# M622X.net
KiCad netlist of a schematic drawn in EAGLE
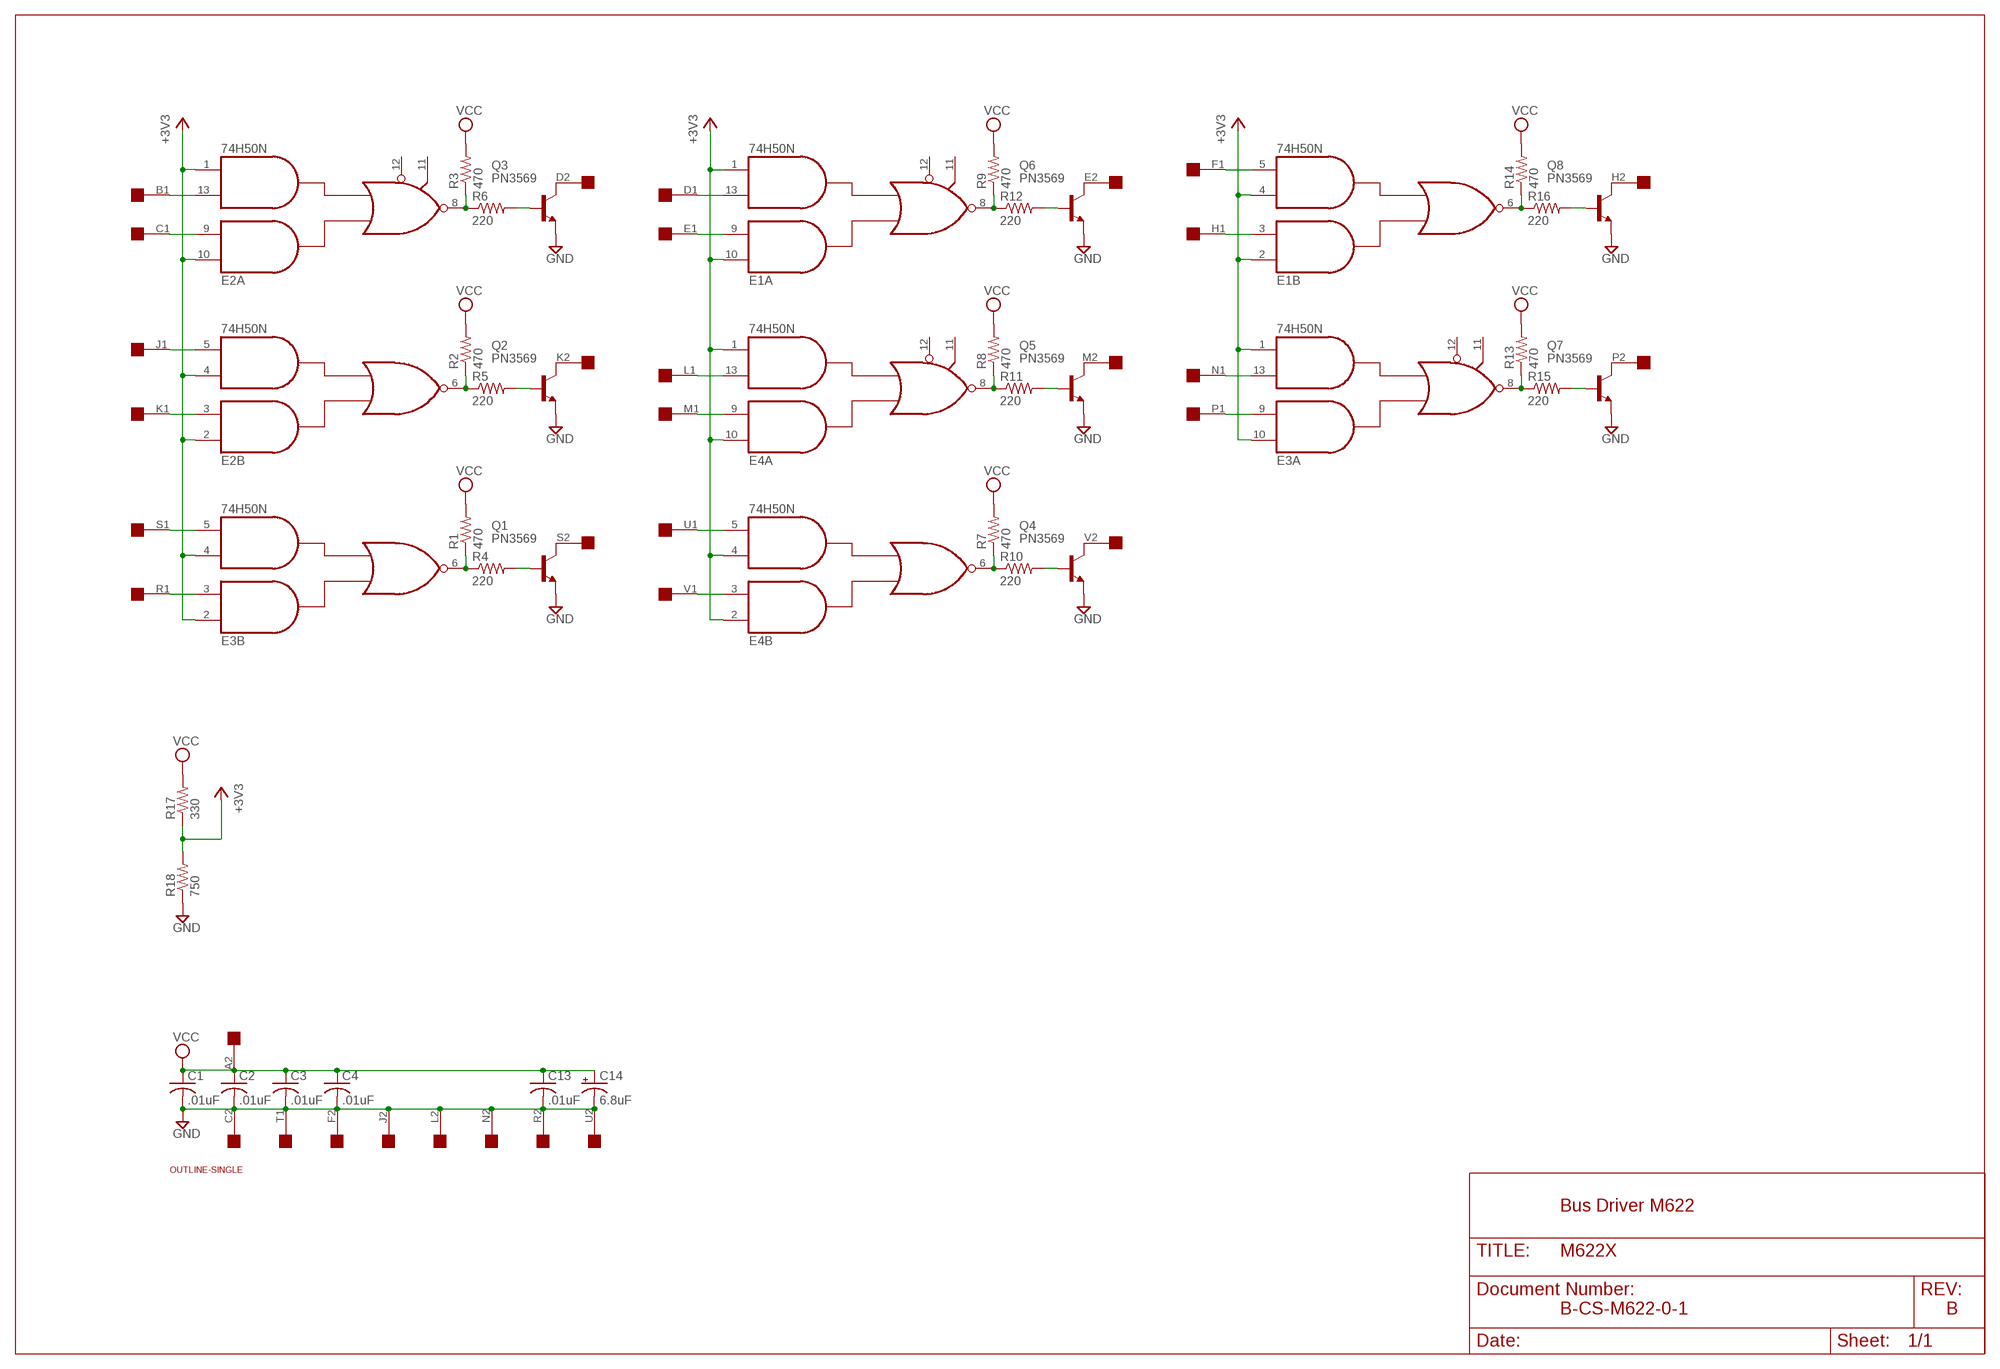
[diagram p0: schematic, sheet 1]

(export (version "E")
  (design (tool "Eeschema 10.0.6"))
  (components
    (comp (ref "C1")
      (value ".01uF")
      (footprint "eagle-import:C050-025X075")
      (libsource (lib "eagle-import") (part "C-US050-025X075"))
    )
    (comp (ref "C2")
      (value ".01uF")
      (footprint "eagle-import:C050-025X075")
      (libsource (lib "eagle-import") (part "C-US050-025X075"))
    )
    (comp (ref "C3")
      (value ".01uF")
      (footprint "eagle-import:C050-025X075")
      (libsource (lib "eagle-import") (part "C-US050-025X075"))
    )
    (comp (ref "C4")
      (value ".01uF")
      (footprint "eagle-import:C050-025X075")
      (libsource (lib "eagle-import") (part "C-US050-025X075"))
    )
    (comp (ref "C13")
      (value ".01uF")
      (footprint "eagle-import:C050-025X075")
      (libsource (lib "eagle-import") (part "C-US050-025X075"))
    )
    (comp (ref "C14")
      (value "6.8uF")
      (footprint "eagle-import:E12-8")
      (libsource (lib "eagle-import") (part "CPOL-USE20-8AXIAL"))
    )
    (comp (ref "E1")
      (value "74H50N")
      (footprint "eagle-import:DIL14")
      (libsource (lib "eagle-import") (part "7450N"))
    )
    (comp (ref "E2")
      (value "74H50N")
      (footprint "eagle-import:DIL14")
      (libsource (lib "eagle-import") (part "7450N"))
    )
    (comp (ref "E3")
      (value "74H50N")
      (footprint "eagle-import:DIL14")
      (libsource (lib "eagle-import") (part "7450N"))
    )
    (comp (ref "E4")
      (value "74H50N")
      (footprint "eagle-import:DIL14")
      (libsource (lib "eagle-import") (part "7450N"))
    )
    (comp (ref "Q1")
      (value "PN3569")
      (footprint "eagle-import:TO5")
      (libsource (lib "eagle-import") (part "2N2102"))
    )
    (comp (ref "Q2")
      (value "PN3569")
      (footprint "eagle-import:TO5")
      (libsource (lib "eagle-import") (part "2N2102"))
    )
    (comp (ref "Q3")
      (value "PN3569")
      (footprint "eagle-import:TO5")
      (libsource (lib "eagle-import") (part "2N2102"))
    )
    (comp (ref "Q4")
      (value "PN3569")
      (footprint "eagle-import:TO5")
      (libsource (lib "eagle-import") (part "2N2102"))
    )
    (comp (ref "Q5")
      (value "PN3569")
      (footprint "eagle-import:TO5")
      (libsource (lib "eagle-import") (part "2N2102"))
    )
    (comp (ref "Q6")
      (value "PN3569")
      (footprint "eagle-import:TO5")
      (libsource (lib "eagle-import") (part "2N2102"))
    )
    (comp (ref "Q7")
      (value "PN3569")
      (footprint "eagle-import:TO5")
      (libsource (lib "eagle-import") (part "2N2102"))
    )
    (comp (ref "Q8")
      (value "PN3569")
      (footprint "eagle-import:TO5")
      (libsource (lib "eagle-import") (part "2N2102"))
    )
    (comp (ref "R1")
      (value "470")
      (footprint "eagle-import:0207_10")
      (libsource (lib "eagle-import") (part "R-US_0207/10"))
    )
    (comp (ref "R2")
      (value "470")
      (footprint "eagle-import:0207_10")
      (libsource (lib "eagle-import") (part "R-US_0207/10"))
    )
    (comp (ref "R3")
      (value "470")
      (footprint "eagle-import:0207_10")
      (libsource (lib "eagle-import") (part "R-US_0207/10"))
    )
    (comp (ref "R4")
      (value "220")
      (footprint "eagle-import:0207_10")
      (libsource (lib "eagle-import") (part "R-US_0207/10"))
    )
    (comp (ref "R5")
      (value "220")
      (footprint "eagle-import:0207_10")
      (libsource (lib "eagle-import") (part "R-US_0207/10"))
    )
    (comp (ref "R6")
      (value "220")
      (footprint "eagle-import:0207_10")
      (libsource (lib "eagle-import") (part "R-US_0207/10"))
    )
    (comp (ref "R7")
      (value "470")
      (footprint "eagle-import:0207_10")
      (libsource (lib "eagle-import") (part "R-US_0207/10"))
    )
    (comp (ref "R8")
      (value "470")
      (footprint "eagle-import:0207_10")
      (libsource (lib "eagle-import") (part "R-US_0207/10"))
    )
    (comp (ref "R9")
      (value "470")
      (footprint "eagle-import:0207_10")
      (libsource (lib "eagle-import") (part "R-US_0207/10"))
    )
    (comp (ref "R10")
      (value "220")
      (footprint "eagle-import:0207_10")
      (libsource (lib "eagle-import") (part "R-US_0207/10"))
    )
    (comp (ref "R11")
      (value "220")
      (footprint "eagle-import:0207_10")
      (libsource (lib "eagle-import") (part "R-US_0207/10"))
    )
    (comp (ref "R12")
      (value "220")
      (footprint "eagle-import:0207_10")
      (libsource (lib "eagle-import") (part "R-US_0207/10"))
    )
    (comp (ref "R13")
      (value "470")
      (footprint "eagle-import:0207_10")
      (libsource (lib "eagle-import") (part "R-US_0207/10"))
    )
    (comp (ref "R14")
      (value "470")
      (footprint "eagle-import:0207_10")
      (libsource (lib "eagle-import") (part "R-US_0207/10"))
    )
    (comp (ref "R15")
      (value "220")
      (footprint "eagle-import:0207_10")
      (libsource (lib "eagle-import") (part "R-US_0207/10"))
    )
    (comp (ref "R16")
      (value "220")
      (footprint "eagle-import:0207_10")
      (libsource (lib "eagle-import") (part "R-US_0207/10"))
    )
    (comp (ref "R17")
      (value "330")
      (footprint "eagle-import:0207_10")
      (libsource (lib "eagle-import") (part "R-US_0207/10"))
    )
    (comp (ref "R18")
      (value "750")
      (footprint "eagle-import:0207_10")
      (libsource (lib "eagle-import") (part "R-US_0207/10"))
    )
    (comp (ref "U$1")
      (value "SINGLE")
      (footprint "eagle-import:EDGE-CON2")
      (libsource (lib "eagle-import") (part "SINGLE"))
    )
    (comp (ref "U$4")
      (value "OUTLINE-SINGLE")
      (footprint "eagle-import:SINGLE")
      (libsource (lib "eagle-import") (part "OUTLINE-SINGLE"))
    )
  )
  (nets
    (net (code "1") (name "+3V3") (class "Default")
      (node (ref "E1") (pin "1") (pinfunction "I4_1") (pintype "input"))
      (node (ref "E1") (pin "10") (pinfunction "I1_10") (pintype "input"))
      (node (ref "E1") (pin "2") (pinfunction "I1_2") (pintype "input"))
      (node (ref "E1") (pin "4") (pinfunction "I3_4") (pintype "input"))
      (node (ref "E2") (pin "1") (pinfunction "I4_1") (pintype "input"))
      (node (ref "E2") (pin "10") (pinfunction "I1_10") (pintype "input"))
      (node (ref "E2") (pin "2") (pinfunction "I1_2") (pintype "input"))
      (node (ref "E2") (pin "4") (pinfunction "I3_4") (pintype "input"))
      (node (ref "E3") (pin "1") (pinfunction "I4_1") (pintype "input"))
      (node (ref "E3") (pin "10") (pinfunction "I1_10") (pintype "input"))
      (node (ref "E3") (pin "2") (pinfunction "I1_2") (pintype "input"))
      (node (ref "E3") (pin "4") (pinfunction "I3_4") (pintype "input"))
      (node (ref "E4") (pin "1") (pinfunction "I4_1") (pintype "input"))
      (node (ref "E4") (pin "10") (pinfunction "I1_10") (pintype "input"))
      (node (ref "E4") (pin "2") (pinfunction "I1_2") (pintype "input"))
      (node (ref "E4") (pin "4") (pinfunction "I3_4") (pintype "input"))
      (node (ref "R17") (pin "1") (pinfunction "1_1") (pintype "passive"))
      (node (ref "R18") (pin "2") (pinfunction "2_2") (pintype "passive"))
    )
    (net (code "2") (name "GND") (class "Default")
      (node (ref "C1") (pin "2") (pinfunction "2_2") (pintype "passive"))
      (node (ref "C13") (pin "2") (pinfunction "2_2") (pintype "passive"))
      (node (ref "C14") (pin "-") (pinfunction "-_-") (pintype "passive"))
      (node (ref "C2") (pin "2") (pinfunction "2_2") (pintype "passive"))
      (node (ref "C3") (pin "2") (pinfunction "2_2") (pintype "passive"))
      (node (ref "C4") (pin "2") (pinfunction "2_2") (pintype "passive"))
      (node (ref "Q1") (pin "1") (pinfunction "E_1") (pintype "passive"))
      (node (ref "Q2") (pin "1") (pinfunction "E_1") (pintype "passive"))
      (node (ref "Q3") (pin "1") (pinfunction "E_1") (pintype "passive"))
      (node (ref "Q4") (pin "1") (pinfunction "E_1") (pintype "passive"))
      (node (ref "Q5") (pin "1") (pinfunction "E_1") (pintype "passive"))
      (node (ref "Q6") (pin "1") (pinfunction "E_1") (pintype "passive"))
      (node (ref "Q7") (pin "1") (pinfunction "E_1") (pintype "passive"))
      (node (ref "Q8") (pin "1") (pinfunction "E_1") (pintype "passive"))
      (node (ref "R18") (pin "1") (pinfunction "1_1") (pintype "passive"))
      (node (ref "U$1") (pin "C2") (pinfunction "1_C2") (pintype "bidirectional"))
      (node (ref "U$1") (pin "F2") (pinfunction "1_F2") (pintype "bidirectional"))
      (node (ref "U$1") (pin "J2") (pinfunction "1_J2") (pintype "bidirectional"))
      (node (ref "U$1") (pin "L2") (pinfunction "1_L2") (pintype "bidirectional"))
      (node (ref "U$1") (pin "N2") (pinfunction "1_N2") (pintype "bidirectional"))
      (node (ref "U$1") (pin "R2") (pinfunction "1_R2") (pintype "bidirectional"))
      (node (ref "U$1") (pin "T1") (pinfunction "1_T1") (pintype "bidirectional"))
      (node (ref "U$1") (pin "U2") (pinfunction "1_U2") (pintype "bidirectional"))
    )
    (net (code "3") (name "Net-(E1A-I2)") (class "Default")
      (node (ref "E1") (pin "9") (pinfunction "I2_9") (pintype "input"))
      (node (ref "U$1") (pin "E1") (pinfunction "1_E1") (pintype "bidirectional"))
    )
    (net (code "4") (name "Net-(E1A-I3)") (class "Default")
      (node (ref "E1") (pin "13") (pinfunction "I3_13") (pintype "input"))
      (node (ref "U$1") (pin "D1") (pinfunction "1_D1") (pintype "bidirectional"))
    )
    (net (code "5") (name "Net-(E1A-O)") (class "Default")
      (node (ref "E1") (pin "8") (pinfunction "O_8") (pintype "output"))
      (node (ref "R12") (pin "1") (pinfunction "1_1") (pintype "passive"))
      (node (ref "R9") (pin "1") (pinfunction "1_1") (pintype "passive"))
    )
    (net (code "6") (name "Net-(E1B-I2)") (class "Default")
      (node (ref "E1") (pin "3") (pinfunction "I2_3") (pintype "input"))
      (node (ref "U$1") (pin "H1") (pinfunction "1_H1") (pintype "bidirectional"))
    )
    (net (code "7") (name "Net-(E1B-I4)") (class "Default")
      (node (ref "E1") (pin "5") (pinfunction "I4_5") (pintype "input"))
      (node (ref "U$1") (pin "F1") (pinfunction "1_F1") (pintype "bidirectional"))
    )
    (net (code "8") (name "Net-(E1B-O)") (class "Default")
      (node (ref "E1") (pin "6") (pinfunction "O_6") (pintype "output"))
      (node (ref "R14") (pin "1") (pinfunction "1_1") (pintype "passive"))
      (node (ref "R16") (pin "1") (pinfunction "1_1") (pintype "passive"))
    )
    (net (code "9") (name "Net-(E2A-I2)") (class "Default")
      (node (ref "E2") (pin "9") (pinfunction "I2_9") (pintype "input"))
      (node (ref "U$1") (pin "C1") (pinfunction "1_C1") (pintype "bidirectional"))
    )
    (net (code "10") (name "Net-(E2A-I3)") (class "Default")
      (node (ref "E2") (pin "13") (pinfunction "I3_13") (pintype "input"))
      (node (ref "U$1") (pin "B1") (pinfunction "1_B1") (pintype "bidirectional"))
    )
    (net (code "11") (name "Net-(E2A-O)") (class "Default")
      (node (ref "E2") (pin "8") (pinfunction "O_8") (pintype "output"))
      (node (ref "R3") (pin "1") (pinfunction "1_1") (pintype "passive"))
      (node (ref "R6") (pin "1") (pinfunction "1_1") (pintype "passive"))
    )
    (net (code "12") (name "Net-(E2B-I2)") (class "Default")
      (node (ref "E2") (pin "3") (pinfunction "I2_3") (pintype "input"))
      (node (ref "U$1") (pin "K1") (pinfunction "1_K1") (pintype "bidirectional"))
    )
    (net (code "13") (name "Net-(E2B-I4)") (class "Default")
      (node (ref "E2") (pin "5") (pinfunction "I4_5") (pintype "input"))
      (node (ref "U$1") (pin "J1") (pinfunction "1_J1") (pintype "bidirectional"))
    )
    (net (code "14") (name "Net-(E2B-O)") (class "Default")
      (node (ref "E2") (pin "6") (pinfunction "O_6") (pintype "output"))
      (node (ref "R2") (pin "1") (pinfunction "1_1") (pintype "passive"))
      (node (ref "R5") (pin "1") (pinfunction "1_1") (pintype "passive"))
    )
    (net (code "15") (name "Net-(E3A-I2)") (class "Default")
      (node (ref "E3") (pin "9") (pinfunction "I2_9") (pintype "input"))
      (node (ref "U$1") (pin "P1") (pinfunction "1_P1") (pintype "bidirectional"))
    )
    (net (code "16") (name "Net-(E3A-I3)") (class "Default")
      (node (ref "E3") (pin "13") (pinfunction "I3_13") (pintype "input"))
      (node (ref "U$1") (pin "N1") (pinfunction "1_N1") (pintype "bidirectional"))
    )
    (net (code "17") (name "Net-(E3A-O)") (class "Default")
      (node (ref "E3") (pin "8") (pinfunction "O_8") (pintype "output"))
      (node (ref "R13") (pin "1") (pinfunction "1_1") (pintype "passive"))
      (node (ref "R15") (pin "1") (pinfunction "1_1") (pintype "passive"))
    )
    (net (code "18") (name "Net-(E3B-I2)") (class "Default")
      (node (ref "E3") (pin "3") (pinfunction "I2_3") (pintype "input"))
      (node (ref "U$1") (pin "R1") (pinfunction "1_R1") (pintype "bidirectional"))
    )
    (net (code "19") (name "Net-(E3B-I4)") (class "Default")
      (node (ref "E3") (pin "5") (pinfunction "I4_5") (pintype "input"))
      (node (ref "U$1") (pin "S1") (pinfunction "1_S1") (pintype "bidirectional"))
    )
    (net (code "20") (name "Net-(E3B-O)") (class "Default")
      (node (ref "E3") (pin "6") (pinfunction "O_6") (pintype "output"))
      (node (ref "R1") (pin "1") (pinfunction "1_1") (pintype "passive"))
      (node (ref "R4") (pin "1") (pinfunction "1_1") (pintype "passive"))
    )
    (net (code "21") (name "Net-(E4A-I2)") (class "Default")
      (node (ref "E4") (pin "9") (pinfunction "I2_9") (pintype "input"))
      (node (ref "U$1") (pin "M1") (pinfunction "1_M1") (pintype "bidirectional"))
    )
    (net (code "22") (name "Net-(E4A-I3)") (class "Default")
      (node (ref "E4") (pin "13") (pinfunction "I3_13") (pintype "input"))
      (node (ref "U$1") (pin "L1") (pinfunction "1_L1") (pintype "bidirectional"))
    )
    (net (code "23") (name "Net-(E4A-O)") (class "Default")
      (node (ref "E4") (pin "8") (pinfunction "O_8") (pintype "output"))
      (node (ref "R11") (pin "1") (pinfunction "1_1") (pintype "passive"))
      (node (ref "R8") (pin "1") (pinfunction "1_1") (pintype "passive"))
    )
    (net (code "24") (name "Net-(E4B-I2)") (class "Default")
      (node (ref "E4") (pin "3") (pinfunction "I2_3") (pintype "input"))
      (node (ref "U$1") (pin "V1") (pinfunction "1_V1") (pintype "bidirectional"))
    )
    (net (code "25") (name "Net-(E4B-I4)") (class "Default")
      (node (ref "E4") (pin "5") (pinfunction "I4_5") (pintype "input"))
      (node (ref "U$1") (pin "U1") (pinfunction "1_U1") (pintype "bidirectional"))
    )
    (net (code "26") (name "Net-(E4B-O)") (class "Default")
      (node (ref "E4") (pin "6") (pinfunction "O_6") (pintype "output"))
      (node (ref "R10") (pin "1") (pinfunction "1_1") (pintype "passive"))
      (node (ref "R7") (pin "1") (pinfunction "1_1") (pintype "passive"))
    )
    (net (code "27") (name "Net-(Q1-B)") (class "Default")
      (node (ref "Q1") (pin "2") (pinfunction "B_2") (pintype "passive"))
      (node (ref "R4") (pin "2") (pinfunction "2_2") (pintype "passive"))
    )
    (net (code "28") (name "Net-(Q1-C)") (class "Default")
      (node (ref "Q1") (pin "3") (pinfunction "C_3") (pintype "passive"))
      (node (ref "U$1") (pin "S2") (pinfunction "1_S2") (pintype "bidirectional"))
    )
    (net (code "29") (name "Net-(Q2-B)") (class "Default")
      (node (ref "Q2") (pin "2") (pinfunction "B_2") (pintype "passive"))
      (node (ref "R5") (pin "2") (pinfunction "2_2") (pintype "passive"))
    )
    (net (code "30") (name "Net-(Q2-C)") (class "Default")
      (node (ref "Q2") (pin "3") (pinfunction "C_3") (pintype "passive"))
      (node (ref "U$1") (pin "K2") (pinfunction "1_K2") (pintype "bidirectional"))
    )
    (net (code "31") (name "Net-(Q3-B)") (class "Default")
      (node (ref "Q3") (pin "2") (pinfunction "B_2") (pintype "passive"))
      (node (ref "R6") (pin "2") (pinfunction "2_2") (pintype "passive"))
    )
    (net (code "32") (name "Net-(Q3-C)") (class "Default")
      (node (ref "Q3") (pin "3") (pinfunction "C_3") (pintype "passive"))
      (node (ref "U$1") (pin "D2") (pinfunction "1_D2") (pintype "bidirectional"))
    )
    (net (code "33") (name "Net-(Q4-B)") (class "Default")
      (node (ref "Q4") (pin "2") (pinfunction "B_2") (pintype "passive"))
      (node (ref "R10") (pin "2") (pinfunction "2_2") (pintype "passive"))
    )
    (net (code "34") (name "Net-(Q4-C)") (class "Default")
      (node (ref "Q4") (pin "3") (pinfunction "C_3") (pintype "passive"))
      (node (ref "U$1") (pin "V2") (pinfunction "1_V2") (pintype "bidirectional"))
    )
    (net (code "35") (name "Net-(Q5-B)") (class "Default")
      (node (ref "Q5") (pin "2") (pinfunction "B_2") (pintype "passive"))
      (node (ref "R11") (pin "2") (pinfunction "2_2") (pintype "passive"))
    )
    (net (code "36") (name "Net-(Q5-C)") (class "Default")
      (node (ref "Q5") (pin "3") (pinfunction "C_3") (pintype "passive"))
      (node (ref "U$1") (pin "M2") (pinfunction "1_M2") (pintype "bidirectional"))
    )
    (net (code "37") (name "Net-(Q6-B)") (class "Default")
      (node (ref "Q6") (pin "2") (pinfunction "B_2") (pintype "passive"))
      (node (ref "R12") (pin "2") (pinfunction "2_2") (pintype "passive"))
    )
    (net (code "38") (name "Net-(Q6-C)") (class "Default")
      (node (ref "Q6") (pin "3") (pinfunction "C_3") (pintype "passive"))
      (node (ref "U$1") (pin "E2") (pinfunction "1_E2") (pintype "bidirectional"))
    )
    (net (code "39") (name "Net-(Q7-B)") (class "Default")
      (node (ref "Q7") (pin "2") (pinfunction "B_2") (pintype "passive"))
      (node (ref "R15") (pin "2") (pinfunction "2_2") (pintype "passive"))
    )
    (net (code "40") (name "Net-(Q7-C)") (class "Default")
      (node (ref "Q7") (pin "3") (pinfunction "C_3") (pintype "passive"))
      (node (ref "U$1") (pin "P2") (pinfunction "1_P2") (pintype "bidirectional"))
    )
    (net (code "41") (name "Net-(Q8-B)") (class "Default")
      (node (ref "Q8") (pin "2") (pinfunction "B_2") (pintype "passive"))
      (node (ref "R16") (pin "2") (pinfunction "2_2") (pintype "passive"))
    )
    (net (code "42") (name "Net-(Q8-C)") (class "Default")
      (node (ref "Q8") (pin "3") (pinfunction "C_3") (pintype "passive"))
      (node (ref "U$1") (pin "H2") (pinfunction "1_H2") (pintype "bidirectional"))
    )
    (net (code "43") (name "VCC") (class "Default")
      (node (ref "C1") (pin "1") (pinfunction "1_1") (pintype "passive"))
      (node (ref "C13") (pin "1") (pinfunction "1_1") (pintype "passive"))
      (node (ref "C14") (pin "+") (pinfunction "+_+") (pintype "passive"))
      (node (ref "C2") (pin "1") (pinfunction "1_1") (pintype "passive"))
      (node (ref "C3") (pin "1") (pinfunction "1_1") (pintype "passive"))
      (node (ref "C4") (pin "1") (pinfunction "1_1") (pintype "passive"))
      (node (ref "R1") (pin "2") (pinfunction "2_2") (pintype "passive"))
      (node (ref "R13") (pin "2") (pinfunction "2_2") (pintype "passive"))
      (node (ref "R14") (pin "2") (pinfunction "2_2") (pintype "passive"))
      (node (ref "R17") (pin "2") (pinfunction "2_2") (pintype "passive"))
      (node (ref "R2") (pin "2") (pinfunction "2_2") (pintype "passive"))
      (node (ref "R3") (pin "2") (pinfunction "2_2") (pintype "passive"))
      (node (ref "R7") (pin "2") (pinfunction "2_2") (pintype "passive"))
      (node (ref "R8") (pin "2") (pinfunction "2_2") (pintype "passive"))
      (node (ref "R9") (pin "2") (pinfunction "2_2") (pintype "passive"))
      (node (ref "U$1") (pin "A2") (pinfunction "1_A2") (pintype "bidirectional"))
    )
    (net (code "44") (name "unconnected-(E1A-I5-Pad12)") (class "Default")
      (node (ref "E1") (pin "12") (pinfunction "I5_12") (pintype "passive"))
    )
    (net (code "45") (name "unconnected-(E1A-I6-Pad11)") (class "Default")
      (node (ref "E1") (pin "11") (pinfunction "I6_11") (pintype "passive"))
    )
    (net (code "46") (name "unconnected-(E2A-I5-Pad12)") (class "Default")
      (node (ref "E2") (pin "12") (pinfunction "I5_12") (pintype "passive"))
    )
    (net (code "47") (name "unconnected-(E2A-I6-Pad11)") (class "Default")
      (node (ref "E2") (pin "11") (pinfunction "I6_11") (pintype "passive"))
    )
    (net (code "48") (name "unconnected-(E3A-I5-Pad12)") (class "Default")
      (node (ref "E3") (pin "12") (pinfunction "I5_12") (pintype "passive"))
    )
    (net (code "49") (name "unconnected-(E3A-I6-Pad11)") (class "Default")
      (node (ref "E3") (pin "11") (pinfunction "I6_11") (pintype "passive"))
    )
    (net (code "50") (name "unconnected-(E4A-I5-Pad12)") (class "Default")
      (node (ref "E4") (pin "12") (pinfunction "I5_12") (pintype "passive"))
    )
    (net (code "51") (name "unconnected-(E4A-I6-Pad11)") (class "Default")
      (node (ref "E4") (pin "11") (pinfunction "I6_11") (pintype "passive"))
    )
  )
)
